# Connectors.net
KiCad netlist of a schematic drawn in Altium Designer
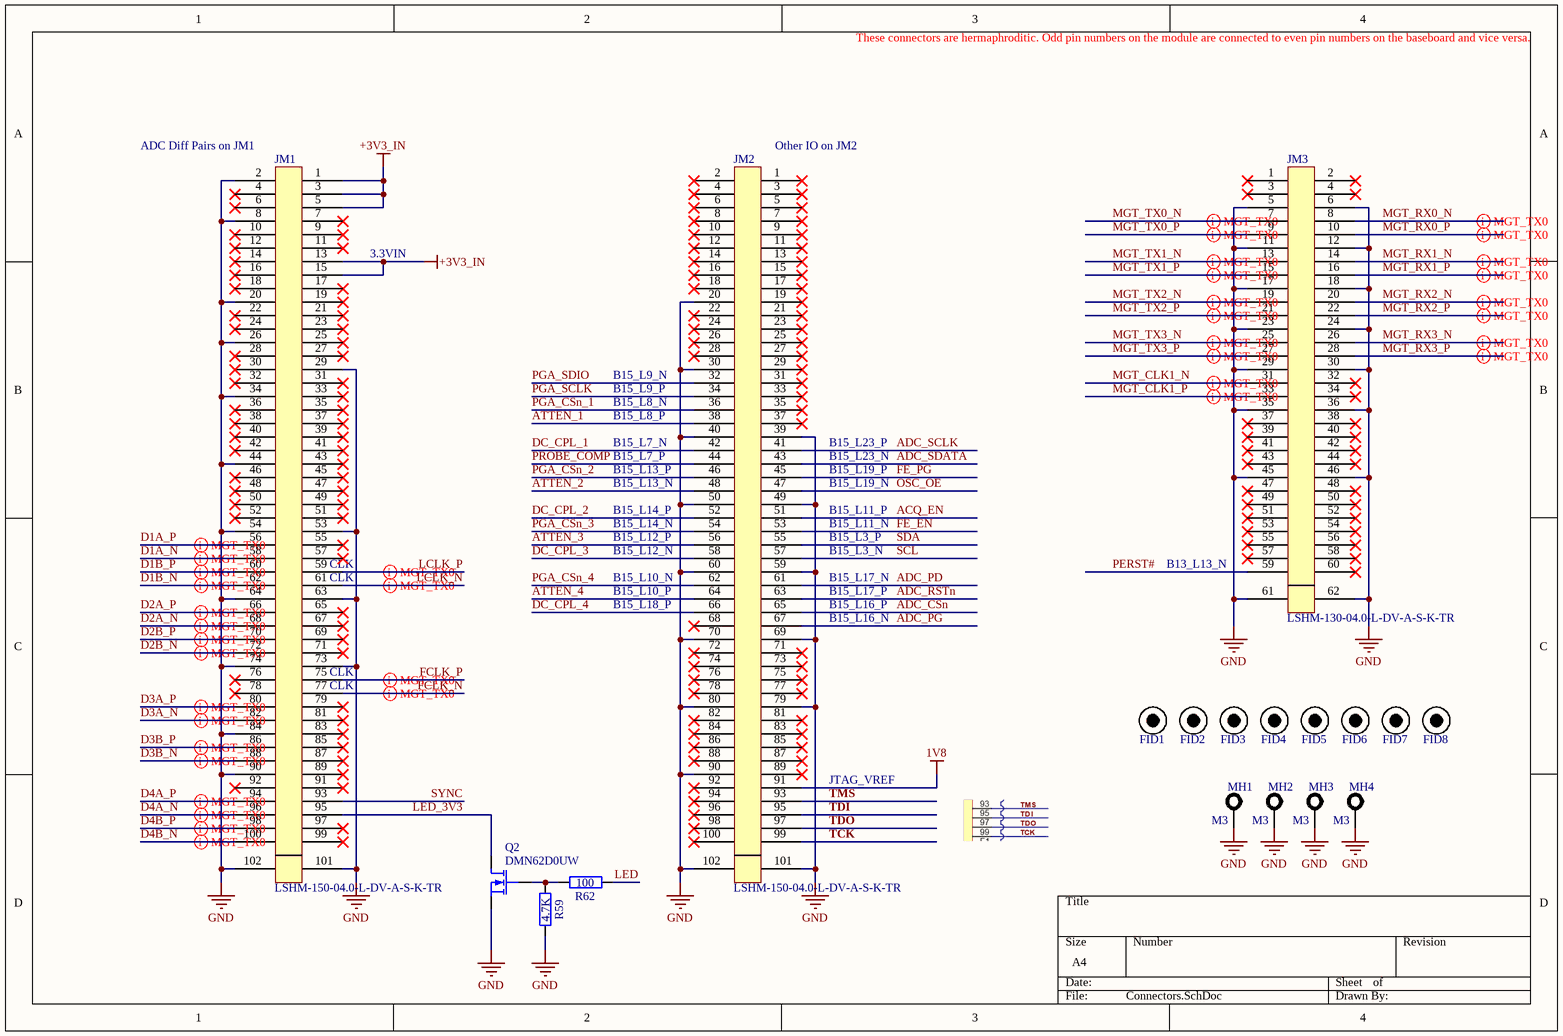
[diagram p0: Connectors.SchDoc]

(export (version "E")
  (design (tool "Eeschema 10.0.6"))
  (components
    (comp (ref "FID1")
      (value "PCB")
      (footprint "GEN_FID")
      (fields (field (name "HOUSE PART NUMBER") "Fiducial-1"))
      (libsource (lib "DSO") (part "FID 1mm"))
    )
    (comp (ref "FID2")
      (value "PCB")
      (footprint "GEN_FID")
      (fields (field (name "HOUSE PART NUMBER") "Fiducial-1"))
      (libsource (lib "DSO") (part "FID 1mm"))
    )
    (comp (ref "FID3")
      (value "PCB")
      (footprint "GEN_FID")
      (fields (field (name "HOUSE PART NUMBER") "Fiducial-1"))
      (libsource (lib "DSO") (part "FID 1mm"))
    )
    (comp (ref "FID4")
      (value "PCB")
      (footprint "GEN_FID")
      (fields (field (name "HOUSE PART NUMBER") "Fiducial-1"))
      (libsource (lib "DSO") (part "FID 1mm"))
    )
    (comp (ref "FID5")
      (value "PCB")
      (footprint "GEN_FID")
      (fields (field (name "HOUSE PART NUMBER") "Fiducial-1"))
      (libsource (lib "DSO") (part "FID 1mm"))
    )
    (comp (ref "FID6")
      (value "PCB")
      (footprint "GEN_FID")
      (fields (field (name "HOUSE PART NUMBER") "Fiducial-1"))
      (libsource (lib "DSO") (part "FID 1mm"))
    )
    (comp (ref "FID7")
      (value "PCB")
      (footprint "GEN_FID")
      (fields (field (name "HOUSE PART NUMBER") "Fiducial-1"))
      (libsource (lib "DSO") (part "FID 1mm"))
    )
    (comp (ref "FID8")
      (value "PCB")
      (footprint "GEN_FID")
      (fields (field (name "HOUSE PART NUMBER") "Fiducial-1"))
      (libsource (lib "DSO") (part "FID 1mm"))
    )
    (comp (ref "JM1")
      (value "LSHM-150-04.0-L-DV-A-S-K-TR")
      (footprint "SAM_LSHM-150-XX.X-XX-DV-A-S")
      (fields (field (name "MANUFACTURER") "Samtec"))
      (libsource (lib "DSO") (part "CONN LSHM-150-04.0-L-DV-A-S-K-TR"))
    )
    (comp (ref "JM2")
      (value "LSHM-150-04.0-L-DV-A-S-K-TR")
      (footprint "SAM_LSHM-150-XX.X-XX-DV-A-S")
      (fields (field (name "MANUFACTURER") "Samtec"))
      (libsource (lib "DSO") (part "CONN LSHM-150-04.0-L-DV-A-S-K-TR"))
    )
    (comp (ref "JM3")
      (value "LSHM-130-04.0-L-DV-A-S-K-TR")
      (footprint "SAM_LSHM-130-XX.X-XX-DV-A-S")
      (fields (field (name "MANUFACTURER") "Samtec"))
      (libsource (lib "DSO") (part "CONN LSHM-130-04.0-L-DV-A-S-K-TR"))
    )
    (comp (ref "MH1") (value "M3") (footprint "MH M3") (libsource (lib "DSO") (part "MH M3")))
    (comp (ref "MH2") (value "M3") (footprint "MH M3") (libsource (lib "DSO") (part "MH M3")))
    (comp (ref "MH3") (value "M3") (footprint "MH M3") (libsource (lib "DSO") (part "MH M3")))
    (comp (ref "MH4") (value "M3") (footprint "MH M3") (libsource (lib "DSO") (part "MH M3")))
    (comp (ref "Q2")
      (value "DMN62D0UW")
      (footprint "GEN_SOT_323")
      (fields (field (name "HOUSE PART NUMBER") "DMN62D0UW-7") (field (name "MANUFACTURER") "Diodes"))
      (libsource (lib "DSO") (part "NMOS DMN62D0UW"))
    )
    (comp (ref "R59")
      (value "4.7K")
      (footprint "GEN_R_0201")
      (fields
        (field (name "TOLERANCE") "1%")
        (field (name "HOUSE PART NUMBER") "R-4.7K-0201-1%-001")
        (field (name "MANUFACTURER") "Yageo")
      )
      (libsource (lib "DSO") (part "RES 4.7K OHM 1% 1/20W 0201"))
    )
    (comp (ref "R62")
      (value "100")
      (footprint "GEN_R_0201")
      (fields
        (field (name "TOLERANCE") "1%")
        (field (name "HOUSE PART NUMBER") "R-100-0201-1%-001")
        (field (name "MANUFACTURER") "Yageo")
      )
      (libsource (lib "DSO") (part "RES 100 OHM 1% 1/20W 0201"))
    )
  )
  (nets
    (net (code "1") (name "+3V3_IN") (class "Default")
      (node (ref "JM1") (pin "1") (pinfunction "1_1") (pintype "passive"))
      (node (ref "JM1") (pin "13") (pinfunction "13_13") (pintype "passive"))
      (node (ref "JM1") (pin "15") (pinfunction "15_15") (pintype "passive"))
      (node (ref "JM1") (pin "3") (pinfunction "3_3") (pintype "passive"))
      (node (ref "JM1") (pin "5") (pinfunction "5_5") (pintype "passive"))
    )
    (net (code "2") (name "/ACQ_EN") (class "Default")
      (node (ref "JM2") (pin "51") (pinfunction "51_51") (pintype "passive"))
    )
    (net (code "3") (name "/ADC_CSn") (class "Default")
      (node (ref "JM2") (pin "65") (pinfunction "65_65") (pintype "passive"))
    )
    (net (code "4") (name "/ADC_PD") (class "Default")
      (node (ref "JM2") (pin "61") (pinfunction "61_61") (pintype "passive"))
    )
    (net (code "5") (name "/ADC_PG") (class "Default")
      (node (ref "JM2") (pin "67") (pinfunction "67_67") (pintype "passive"))
    )
    (net (code "6") (name "/ADC_RSTn") (class "Default")
      (node (ref "JM2") (pin "63") (pinfunction "63_63") (pintype "passive"))
    )
    (net (code "7") (name "/ADC_SCLK") (class "Default")
      (node (ref "JM2") (pin "41") (pinfunction "41_41") (pintype "passive"))
    )
    (net (code "8") (name "/ADC_SDATA") (class "Default")
      (node (ref "JM2") (pin "43") (pinfunction "43_43") (pintype "passive"))
    )
    (net (code "9") (name "/ATTEN_1") (class "Default")
      (node (ref "JM2") (pin "38") (pinfunction "38_38") (pintype "passive"))
    )
    (net (code "10") (name "/ATTEN_2") (class "Default")
      (node (ref "JM2") (pin "48") (pinfunction "48_48") (pintype "passive"))
    )
    (net (code "11") (name "/ATTEN_3") (class "Default")
      (node (ref "JM2") (pin "56") (pinfunction "56_56") (pintype "passive"))
    )
    (net (code "12") (name "/ATTEN_4") (class "Default")
      (node (ref "JM2") (pin "64") (pinfunction "64_64") (pintype "passive"))
    )
    (net (code "13") (name "/D1A_N") (class "Default")
      (node (ref "JM1") (pin "58") (pinfunction "58_58") (pintype "passive"))
    )
    (net (code "14") (name "/D1A_P") (class "Default")
      (node (ref "JM1") (pin "56") (pinfunction "56_56") (pintype "passive"))
    )
    (net (code "15") (name "/D1B_N") (class "Default")
      (node (ref "JM1") (pin "62") (pinfunction "62_62") (pintype "passive"))
    )
    (net (code "16") (name "/D1B_P") (class "Default")
      (node (ref "JM1") (pin "60") (pinfunction "60_60") (pintype "passive"))
    )
    (net (code "17") (name "/D2A_N") (class "Default")
      (node (ref "JM1") (pin "68") (pinfunction "68_68") (pintype "passive"))
    )
    (net (code "18") (name "/D2A_P") (class "Default")
      (node (ref "JM1") (pin "66") (pinfunction "66_66") (pintype "passive"))
    )
    (net (code "19") (name "/D2B_N") (class "Default")
      (node (ref "JM1") (pin "72") (pinfunction "72_72") (pintype "passive"))
    )
    (net (code "20") (name "/D2B_P") (class "Default")
      (node (ref "JM1") (pin "70") (pinfunction "70_70") (pintype "passive"))
    )
    (net (code "21") (name "/D3A_N") (class "Default")
      (node (ref "JM1") (pin "82") (pinfunction "82_82") (pintype "passive"))
    )
    (net (code "22") (name "/D3A_P") (class "Default")
      (node (ref "JM1") (pin "80") (pinfunction "80_80") (pintype "passive"))
    )
    (net (code "23") (name "/D3B_N") (class "Default")
      (node (ref "JM1") (pin "88") (pinfunction "88_88") (pintype "passive"))
    )
    (net (code "24") (name "/D3B_P") (class "Default")
      (node (ref "JM1") (pin "86") (pinfunction "86_86") (pintype "passive"))
    )
    (net (code "25") (name "/D4A_N") (class "Default")
      (node (ref "JM1") (pin "96") (pinfunction "96_96") (pintype "passive"))
    )
    (net (code "26") (name "/D4A_P") (class "Default")
      (node (ref "JM1") (pin "94") (pinfunction "94_94") (pintype "passive"))
    )
    (net (code "27") (name "/D4B_N") (class "Default")
      (node (ref "JM1") (pin "100") (pinfunction "100_100") (pintype "passive"))
    )
    (net (code "28") (name "/D4B_P") (class "Default")
      (node (ref "JM1") (pin "98") (pinfunction "98_98") (pintype "passive"))
    )
    (net (code "29") (name "/DC_CPL_1") (class "Default")
      (node (ref "JM2") (pin "42") (pinfunction "42_42") (pintype "passive"))
    )
    (net (code "30") (name "/DC_CPL_2") (class "Default")
      (node (ref "JM2") (pin "52") (pinfunction "52_52") (pintype "passive"))
    )
    (net (code "31") (name "/DC_CPL_3") (class "Default")
      (node (ref "JM2") (pin "58") (pinfunction "58_58") (pintype "passive"))
    )
    (net (code "32") (name "/DC_CPL_4") (class "Default")
      (node (ref "JM2") (pin "66") (pinfunction "66_66") (pintype "passive"))
    )
    (net (code "33") (name "/FCLK_N") (class "Default")
      (node (ref "JM1") (pin "77") (pinfunction "77_77") (pintype "passive"))
    )
    (net (code "34") (name "/FCLK_P") (class "Default")
      (node (ref "JM1") (pin "75") (pinfunction "75_75") (pintype "passive"))
    )
    (net (code "35") (name "/FE_EN") (class "Default")
      (node (ref "JM2") (pin "53") (pinfunction "53_53") (pintype "passive"))
    )
    (net (code "36") (name "/FE_PG") (class "Default")
      (node (ref "JM2") (pin "45") (pinfunction "45_45") (pintype "passive"))
    )
    (net (code "37") (name "/LCLK_N") (class "Default")
      (node (ref "JM1") (pin "61") (pinfunction "61_61") (pintype "passive"))
    )
    (net (code "38") (name "/LCLK_P") (class "Default")
      (node (ref "JM1") (pin "59") (pinfunction "59_59") (pintype "passive"))
    )
    (net (code "39") (name "/LED") (class "Default")
      (node (ref "R62") (pin "1") (pinfunction "1_1") (pintype "passive"))
    )
    (net (code "40") (name "/LED_3V3") (class "Default")
      (node (ref "JM1") (pin "95") (pinfunction "95_95") (pintype "passive"))
      (node (ref "Q2") (pin "1") (pinfunction "D_1") (pintype "passive"))
    )
    (net (code "41") (name "/MGT_CLK1_N") (class "Default")
      (node (ref "JM3") (pin "31") (pinfunction "31_31") (pintype "passive"))
    )
    (net (code "42") (name "/MGT_CLK1_P") (class "Default")
      (node (ref "JM3") (pin "33") (pinfunction "33_33") (pintype "passive"))
    )
    (net (code "43") (name "/MGT_RX0_N") (class "Default")
      (node (ref "JM3") (pin "8") (pinfunction "8_8") (pintype "passive"))
    )
    (net (code "44") (name "/MGT_RX0_P") (class "Default")
      (node (ref "JM3") (pin "10") (pinfunction "10_10") (pintype "passive"))
    )
    (net (code "45") (name "/MGT_RX1_N") (class "Default")
      (node (ref "JM3") (pin "14") (pinfunction "14_14") (pintype "passive"))
    )
    (net (code "46") (name "/MGT_RX1_P") (class "Default")
      (node (ref "JM3") (pin "16") (pinfunction "16_16") (pintype "passive"))
    )
    (net (code "47") (name "/MGT_RX2_N") (class "Default")
      (node (ref "JM3") (pin "20") (pinfunction "20_20") (pintype "passive"))
    )
    (net (code "48") (name "/MGT_RX2_P") (class "Default")
      (node (ref "JM3") (pin "22") (pinfunction "22_22") (pintype "passive"))
    )
    (net (code "49") (name "/MGT_RX3_N") (class "Default")
      (node (ref "JM3") (pin "26") (pinfunction "26_26") (pintype "passive"))
    )
    (net (code "50") (name "/MGT_RX3_P") (class "Default")
      (node (ref "JM3") (pin "28") (pinfunction "28_28") (pintype "passive"))
    )
    (net (code "51") (name "/MGT_TX0_N") (class "Default")
      (node (ref "JM3") (pin "7") (pinfunction "7_7") (pintype "passive"))
    )
    (net (code "52") (name "/MGT_TX0_P") (class "Default")
      (node (ref "JM3") (pin "9") (pinfunction "9_9") (pintype "passive"))
    )
    (net (code "53") (name "/MGT_TX1_N") (class "Default")
      (node (ref "JM3") (pin "13") (pinfunction "13_13") (pintype "passive"))
    )
    (net (code "54") (name "/MGT_TX1_P") (class "Default")
      (node (ref "JM3") (pin "15") (pinfunction "15_15") (pintype "passive"))
    )
    (net (code "55") (name "/MGT_TX2_N") (class "Default")
      (node (ref "JM3") (pin "19") (pinfunction "19_19") (pintype "passive"))
    )
    (net (code "56") (name "/MGT_TX2_P") (class "Default")
      (node (ref "JM3") (pin "21") (pinfunction "21_21") (pintype "passive"))
    )
    (net (code "57") (name "/MGT_TX3_N") (class "Default")
      (node (ref "JM3") (pin "25") (pinfunction "25_25") (pintype "passive"))
    )
    (net (code "58") (name "/MGT_TX3_P") (class "Default")
      (node (ref "JM3") (pin "27") (pinfunction "27_27") (pintype "passive"))
    )
    (net (code "59") (name "/OSC_OE") (class "Default")
      (node (ref "JM2") (pin "47") (pinfunction "47_47") (pintype "passive"))
    )
    (net (code "60") (name "/PERST#") (class "Default")
      (node (ref "JM3") (pin "59") (pinfunction "59_59") (pintype "passive"))
    )
    (net (code "61") (name "/PGA_CSn_1") (class "Default")
      (node (ref "JM2") (pin "36") (pinfunction "36_36") (pintype "passive"))
    )
    (net (code "62") (name "/PGA_CSn_2") (class "Default")
      (node (ref "JM2") (pin "46") (pinfunction "46_46") (pintype "passive"))
    )
    (net (code "63") (name "/PGA_CSn_3") (class "Default")
      (node (ref "JM2") (pin "54") (pinfunction "54_54") (pintype "passive"))
    )
    (net (code "64") (name "/PGA_CSn_4") (class "Default")
      (node (ref "JM2") (pin "62") (pinfunction "62_62") (pintype "passive"))
    )
    (net (code "65") (name "/PGA_SCLK") (class "Default")
      (node (ref "JM2") (pin "34") (pinfunction "34_34") (pintype "passive"))
    )
    (net (code "66") (name "/PGA_SDIO") (class "Default")
      (node (ref "JM2") (pin "32") (pinfunction "32_32") (pintype "passive"))
    )
    (net (code "67") (name "/PROBE_COMP") (class "Default")
      (node (ref "JM2") (pin "44") (pinfunction "44_44") (pintype "passive"))
    )
    (net (code "68") (name "/SCL") (class "Default")
      (node (ref "JM2") (pin "57") (pinfunction "57_57") (pintype "passive"))
    )
    (net (code "69") (name "/SDA") (class "Default")
      (node (ref "JM2") (pin "55") (pinfunction "55_55") (pintype "passive"))
    )
    (net (code "70") (name "/SYNC") (class "Default")
      (node (ref "JM1") (pin "93") (pinfunction "93_93") (pintype "passive"))
    )
    (net (code "71") (name "/TCK") (class "Default")
      (node (ref "JM2") (pin "99") (pinfunction "99_99") (pintype "passive"))
    )
    (net (code "72") (name "/TDI") (class "Default")
      (node (ref "JM2") (pin "95") (pinfunction "95_95") (pintype "passive"))
    )
    (net (code "73") (name "/TDO") (class "Default")
      (node (ref "JM2") (pin "97") (pinfunction "97_97") (pintype "passive"))
    )
    (net (code "74") (name "/TMS") (class "Default")
      (node (ref "JM2") (pin "93") (pinfunction "93_93") (pintype "passive"))
    )
    (net (code "75") (name "1V8") (class "Default")
      (node (ref "JM2") (pin "91") (pinfunction "91_91") (pintype "passive"))
    )
    (net (code "76") (name "GND") (class "Default")
      (node (ref "JM1") (pin "101") (pinfunction "101_101") (pintype "passive"))
      (node (ref "JM1") (pin "102") (pinfunction "102_102") (pintype "passive"))
      (node (ref "JM1") (pin "2") (pinfunction "2_2") (pintype "passive"))
      (node (ref "JM1") (pin "20") (pinfunction "20_20") (pintype "passive"))
      (node (ref "JM1") (pin "26") (pinfunction "26_26") (pintype "passive"))
      (node (ref "JM1") (pin "29") (pinfunction "29_29") (pintype "passive"))
      (node (ref "JM1") (pin "34") (pinfunction "34_34") (pintype "passive"))
      (node (ref "JM1") (pin "44") (pinfunction "44_44") (pintype "passive"))
      (node (ref "JM1") (pin "53") (pinfunction "53_53") (pintype "passive"))
      (node (ref "JM1") (pin "54") (pinfunction "54_54") (pintype "passive"))
      (node (ref "JM1") (pin "63") (pinfunction "63_63") (pintype "passive"))
      (node (ref "JM1") (pin "64") (pinfunction "64_64") (pintype "passive"))
      (node (ref "JM1") (pin "73") (pinfunction "73_73") (pintype "passive"))
      (node (ref "JM1") (pin "74") (pinfunction "74_74") (pintype "passive"))
      (node (ref "JM1") (pin "8") (pinfunction "8_8") (pintype "passive"))
      (node (ref "JM1") (pin "84") (pinfunction "84_84") (pintype "passive"))
      (node (ref "JM1") (pin "90") (pinfunction "90_90") (pintype "passive"))
      (node (ref "JM2") (pin "101") (pinfunction "101_101") (pintype "passive"))
      (node (ref "JM2") (pin "102") (pinfunction "102_102") (pintype "passive"))
      (node (ref "JM2") (pin "20") (pinfunction "20_20") (pintype "passive"))
      (node (ref "JM2") (pin "30") (pinfunction "30_30") (pintype "passive"))
      (node (ref "JM2") (pin "39") (pinfunction "39_39") (pintype "passive"))
      (node (ref "JM2") (pin "40") (pinfunction "40_40") (pintype "passive"))
      (node (ref "JM2") (pin "49") (pinfunction "49_49") (pintype "passive"))
      (node (ref "JM2") (pin "50") (pinfunction "50_50") (pintype "passive"))
      (node (ref "JM2") (pin "59") (pinfunction "59_59") (pintype "passive"))
      (node (ref "JM2") (pin "60") (pinfunction "60_60") (pintype "passive"))
      (node (ref "JM2") (pin "69") (pinfunction "69_69") (pintype "passive"))
      (node (ref "JM2") (pin "70") (pinfunction "70_70") (pintype "passive"))
      (node (ref "JM2") (pin "79") (pinfunction "79_79") (pintype "passive"))
      (node (ref "JM2") (pin "80") (pinfunction "80_80") (pintype "passive"))
      (node (ref "JM2") (pin "90") (pinfunction "90_90") (pintype "passive"))
      (node (ref "JM3") (pin "11") (pinfunction "11_11") (pintype "passive"))
      (node (ref "JM3") (pin "12") (pinfunction "12_12") (pintype "passive"))
      (node (ref "JM3") (pin "17") (pinfunction "17_17") (pintype "passive"))
      (node (ref "JM3") (pin "18") (pinfunction "18_18") (pintype "passive"))
      (node (ref "JM3") (pin "23") (pinfunction "23_23") (pintype "passive"))
      (node (ref "JM3") (pin "24") (pinfunction "24_24") (pintype "passive"))
      (node (ref "JM3") (pin "29") (pinfunction "29_29") (pintype "passive"))
      (node (ref "JM3") (pin "30") (pinfunction "30_30") (pintype "passive"))
      (node (ref "JM3") (pin "35") (pinfunction "35_35") (pintype "passive"))
      (node (ref "JM3") (pin "36") (pinfunction "36_36") (pintype "passive"))
      (node (ref "JM3") (pin "45") (pinfunction "45_45") (pintype "passive"))
      (node (ref "JM3") (pin "46") (pinfunction "46_46") (pintype "passive"))
      (node (ref "JM3") (pin "5") (pinfunction "5_5") (pintype "passive"))
      (node (ref "JM3") (pin "6") (pinfunction "6_6") (pintype "passive"))
      (node (ref "JM3") (pin "61") (pinfunction "61_61") (pintype "passive"))
      (node (ref "JM3") (pin "62") (pinfunction "62_62") (pintype "passive"))
      (node (ref "MH1") (pin "1") (pinfunction "1_1") (pintype "passive"))
      (node (ref "MH2") (pin "1") (pinfunction "1_1") (pintype "passive"))
      (node (ref "MH3") (pin "1") (pinfunction "1_1") (pintype "passive"))
      (node (ref "MH4") (pin "1") (pinfunction "1_1") (pintype "passive"))
      (node (ref "Q2") (pin "3") (pinfunction "S_3") (pintype "passive"))
      (node (ref "R59") (pin "2") (pinfunction "2_2") (pintype "passive"))
    )
    (net (code "77") (name "Net-(Q2-G)") (class "Default")
      (node (ref "Q2") (pin "2") (pinfunction "G_2") (pintype "passive"))
      (node (ref "R59") (pin "1") (pinfunction "1_1") (pintype "passive"))
      (node (ref "R62") (pin "2") (pinfunction "2_2") (pintype "passive"))
    )
    (net (code "78") (name "unconnected-(JM1-Pad4)") (class "Default")
      (node (ref "JM1") (pin "4") (pinfunction "4_4") (pintype "passive+no_connect"))
    )
    (net (code "79") (name "unconnected-(JM1-Pad6)") (class "Default")
      (node (ref "JM1") (pin "6") (pinfunction "6_6") (pintype "passive+no_connect"))
    )
    (net (code "80") (name "unconnected-(JM1-Pad7)") (class "Default")
      (node (ref "JM1") (pin "7") (pinfunction "7_7") (pintype "passive+no_connect"))
    )
    (net (code "81") (name "unconnected-(JM1-Pad9)") (class "Default")
      (node (ref "JM1") (pin "9") (pinfunction "9_9") (pintype "passive+no_connect"))
    )
    (net (code "82") (name "unconnected-(JM1-Pad10)") (class "Default")
      (node (ref "JM1") (pin "10") (pinfunction "10_10") (pintype "passive+no_connect"))
    )
    (net (code "83") (name "unconnected-(JM1-Pad11)") (class "Default")
      (node (ref "JM1") (pin "11") (pinfunction "11_11") (pintype "passive+no_connect"))
    )
    (net (code "84") (name "unconnected-(JM1-Pad12)") (class "Default")
      (node (ref "JM1") (pin "12") (pinfunction "12_12") (pintype "passive+no_connect"))
    )
    (net (code "85") (name "unconnected-(JM1-Pad14)") (class "Default")
      (node (ref "JM1") (pin "14") (pinfunction "14_14") (pintype "passive+no_connect"))
    )
    (net (code "86") (name "unconnected-(JM1-Pad16)") (class "Default")
      (node (ref "JM1") (pin "16") (pinfunction "16_16") (pintype "passive+no_connect"))
    )
    (net (code "87") (name "unconnected-(JM1-Pad17)") (class "Default")
      (node (ref "JM1") (pin "17") (pinfunction "17_17") (pintype "passive+no_connect"))
    )
    (net (code "88") (name "unconnected-(JM1-Pad18)") (class "Default")
      (node (ref "JM1") (pin "18") (pinfunction "18_18") (pintype "passive+no_connect"))
    )
    (net (code "89") (name "unconnected-(JM1-Pad19)") (class "Default")
      (node (ref "JM1") (pin "19") (pinfunction "19_19") (pintype "passive+no_connect"))
    )
    (net (code "90") (name "unconnected-(JM1-Pad21)") (class "Default")
      (node (ref "JM1") (pin "21") (pinfunction "21_21") (pintype "passive+no_connect"))
    )
    (net (code "91") (name "unconnected-(JM1-Pad22)") (class "Default")
      (node (ref "JM1") (pin "22") (pinfunction "22_22") (pintype "passive+no_connect"))
    )
    (net (code "92") (name "unconnected-(JM1-Pad23)") (class "Default")
      (node (ref "JM1") (pin "23") (pinfunction "23_23") (pintype "passive+no_connect"))
    )
    (net (code "93") (name "unconnected-(JM1-Pad24)") (class "Default")
      (node (ref "JM1") (pin "24") (pinfunction "24_24") (pintype "passive+no_connect"))
    )
    (net (code "94") (name "unconnected-(JM1-Pad25)") (class "Default")
      (node (ref "JM1") (pin "25") (pinfunction "25_25") (pintype "passive+no_connect"))
    )
    (net (code "95") (name "unconnected-(JM1-Pad27)") (class "Default")
      (node (ref "JM1") (pin "27") (pinfunction "27_27") (pintype "passive+no_connect"))
    )
    (net (code "96") (name "unconnected-(JM1-Pad28)") (class "Default")
      (node (ref "JM1") (pin "28") (pinfunction "28_28") (pintype "passive+no_connect"))
    )
    (net (code "97") (name "unconnected-(JM1-Pad30)") (class "Default")
      (node (ref "JM1") (pin "30") (pinfunction "30_30") (pintype "passive+no_connect"))
    )
    (net (code "98") (name "unconnected-(JM1-Pad31)") (class "Default")
      (node (ref "JM1") (pin "31") (pinfunction "31_31") (pintype "passive+no_connect"))
    )
    (net (code "99") (name "unconnected-(JM1-Pad32)") (class "Default")
      (node (ref "JM1") (pin "32") (pinfunction "32_32") (pintype "passive+no_connect"))
    )
    (net (code "100") (name "unconnected-(JM1-Pad33)") (class "Default")
      (node (ref "JM1") (pin "33") (pinfunction "33_33") (pintype "passive+no_connect"))
    )
    (net (code "101") (name "unconnected-(JM1-Pad35)") (class "Default")
      (node (ref "JM1") (pin "35") (pinfunction "35_35") (pintype "passive+no_connect"))
    )
    (net (code "102") (name "unconnected-(JM1-Pad36)") (class "Default")
      (node (ref "JM1") (pin "36") (pinfunction "36_36") (pintype "passive+no_connect"))
    )
    (net (code "103") (name "unconnected-(JM1-Pad37)") (class "Default")
      (node (ref "JM1") (pin "37") (pinfunction "37_37") (pintype "passive+no_connect"))
    )
    (net (code "104") (name "unconnected-(JM1-Pad38)") (class "Default")
      (node (ref "JM1") (pin "38") (pinfunction "38_38") (pintype "passive+no_connect"))
    )
    (net (code "105") (name "unconnected-(JM1-Pad39)") (class "Default")
      (node (ref "JM1") (pin "39") (pinfunction "39_39") (pintype "passive+no_connect"))
    )
    (net (code "106") (name "unconnected-(JM1-Pad40)") (class "Default")
      (node (ref "JM1") (pin "40") (pinfunction "40_40") (pintype "passive+no_connect"))
    )
    (net (code "107") (name "unconnected-(JM1-Pad41)") (class "Default")
      (node (ref "JM1") (pin "41") (pinfunction "41_41") (pintype "passive+no_connect"))
    )
    (net (code "108") (name "unconnected-(JM1-Pad42)") (class "Default")
      (node (ref "JM1") (pin "42") (pinfunction "42_42") (pintype "passive+no_connect"))
    )
    (net (code "109") (name "unconnected-(JM1-Pad43)") (class "Default")
      (node (ref "JM1") (pin "43") (pinfunction "43_43") (pintype "passive+no_connect"))
    )
    (net (code "110") (name "unconnected-(JM1-Pad45)") (class "Default")
      (node (ref "JM1") (pin "45") (pinfunction "45_45") (pintype "passive+no_connect"))
    )
    (net (code "111") (name "unconnected-(JM1-Pad46)") (class "Default")
      (node (ref "JM1") (pin "46") (pinfunction "46_46") (pintype "passive+no_connect"))
    )
    (net (code "112") (name "unconnected-(JM1-Pad47)") (class "Default")
      (node (ref "JM1") (pin "47") (pinfunction "47_47") (pintype "passive+no_connect"))
    )
    (net (code "113") (name "unconnected-(JM1-Pad48)") (class "Default")
      (node (ref "JM1") (pin "48") (pinfunction "48_48") (pintype "passive+no_connect"))
    )
    (net (code "114") (name "unconnected-(JM1-Pad49)") (class "Default")
      (node (ref "JM1") (pin "49") (pinfunction "49_49") (pintype "passive+no_connect"))
    )
    (net (code "115") (name "unconnected-(JM1-Pad50)") (class "Default")
      (node (ref "JM1") (pin "50") (pinfunction "50_50") (pintype "passive+no_connect"))
    )
    (net (code "116") (name "unconnected-(JM1-Pad51)") (class "Default")
      (node (ref "JM1") (pin "51") (pinfunction "51_51") (pintype "passive+no_connect"))
    )
    (net (code "117") (name "unconnected-(JM1-Pad52)") (class "Default")
      (node (ref "JM1") (pin "52") (pinfunction "52_52") (pintype "passive+no_connect"))
    )
    (net (code "118") (name "unconnected-(JM1-Pad55)") (class "Default")
      (node (ref "JM1") (pin "55") (pinfunction "55_55") (pintype "passive+no_connect"))
    )
    (net (code "119") (name "unconnected-(JM1-Pad57)") (class "Default")
      (node (ref "JM1") (pin "57") (pinfunction "57_57") (pintype "passive+no_connect"))
    )
    (net (code "120") (name "unconnected-(JM1-Pad65)") (class "Default")
      (node (ref "JM1") (pin "65") (pinfunction "65_65") (pintype "passive+no_connect"))
    )
    (net (code "121") (name "unconnected-(JM1-Pad67)") (class "Default")
      (node (ref "JM1") (pin "67") (pinfunction "67_67") (pintype "passive+no_connect"))
    )
    (net (code "122") (name "unconnected-(JM1-Pad69)") (class "Default")
      (node (ref "JM1") (pin "69") (pinfunction "69_69") (pintype "passive+no_connect"))
    )
    (net (code "123") (name "unconnected-(JM1-Pad71)") (class "Default")
      (node (ref "JM1") (pin "71") (pinfunction "71_71") (pintype "passive+no_connect"))
    )
    (net (code "124") (name "unconnected-(JM1-Pad76)") (class "Default")
      (node (ref "JM1") (pin "76") (pinfunction "76_76") (pintype "passive+no_connect"))
    )
    (net (code "125") (name "unconnected-(JM1-Pad78)") (class "Default")
      (node (ref "JM1") (pin "78") (pinfunction "78_78") (pintype "passive+no_connect"))
    )
    (net (code "126") (name "unconnected-(JM1-Pad79)") (class "Default")
      (node (ref "JM1") (pin "79") (pinfunction "79_79") (pintype "passive+no_connect"))
    )
    (net (code "127") (name "unconnected-(JM1-Pad81)") (class "Default")
      (node (ref "JM1") (pin "81") (pinfunction "81_81") (pintype "passive+no_connect"))
    )
    (net (code "128") (name "unconnected-(JM1-Pad83)") (class "Default")
      (node (ref "JM1") (pin "83") (pinfunction "83_83") (pintype "passive+no_connect"))
    )
    (net (code "129") (name "unconnected-(JM1-Pad85)") (class "Default")
      (node (ref "JM1") (pin "85") (pinfunction "85_85") (pintype "passive+no_connect"))
    )
    (net (code "130") (name "unconnected-(JM1-Pad87)") (class "Default")
      (node (ref "JM1") (pin "87") (pinfunction "87_87") (pintype "passive+no_connect"))
    )
    (net (code "131") (name "unconnected-(JM1-Pad89)") (class "Default")
      (node (ref "JM1") (pin "89") (pinfunction "89_89") (pintype "passive+no_connect"))
    )
    (net (code "132") (name "unconnected-(JM1-Pad91)") (class "Default")
      (node (ref "JM1") (pin "91") (pinfunction "91_91") (pintype "passive+no_connect"))
    )
    (net (code "133") (name "unconnected-(JM1-Pad92)") (class "Default")
      (node (ref "JM1") (pin "92") (pinfunction "92_92") (pintype "passive+no_connect"))
    )
    (net (code "134") (name "unconnected-(JM1-Pad97)") (class "Default")
      (node (ref "JM1") (pin "97") (pinfunction "97_97") (pintype "passive+no_connect"))
    )
    (net (code "135") (name "unconnected-(JM1-Pad99)") (class "Default")
      (node (ref "JM1") (pin "99") (pinfunction "99_99") (pintype "passive+no_connect"))
    )
    (net (code "136") (name "unconnected-(JM2-Pad1)") (class "Default")
      (node (ref "JM2") (pin "1") (pinfunction "1_1") (pintype "passive+no_connect"))
    )
    (net (code "137") (name "unconnected-(JM2-Pad2)") (class "Default")
      (node (ref "JM2") (pin "2") (pinfunction "2_2") (pintype "passive+no_connect"))
    )
    (net (code "138") (name "unconnected-(JM2-Pad3)") (class "Default")
      (node (ref "JM2") (pin "3") (pinfunction "3_3") (pintype "passive+no_connect"))
    )
    (net (code "139") (name "unconnected-(JM2-Pad4)") (class "Default")
      (node (ref "JM2") (pin "4") (pinfunction "4_4") (pintype "passive+no_connect"))
    )
    (net (code "140") (name "unconnected-(JM2-Pad5)") (class "Default")
      (node (ref "JM2") (pin "5") (pinfunction "5_5") (pintype "passive+no_connect"))
    )
    (net (code "141") (name "unconnected-(JM2-Pad6)") (class "Default")
      (node (ref "JM2") (pin "6") (pinfunction "6_6") (pintype "passive+no_connect"))
    )
    (net (code "142") (name "unconnected-(JM2-Pad7)") (class "Default")
      (node (ref "JM2") (pin "7") (pinfunction "7_7") (pintype "passive+no_connect"))
    )
    (net (code "143") (name "unconnected-(JM2-Pad8)") (class "Default")
      (node (ref "JM2") (pin "8") (pinfunction "8_8") (pintype "passive+no_connect"))
    )
    (net (code "144") (name "unconnected-(JM2-Pad9)") (class "Default")
      (node (ref "JM2") (pin "9") (pinfunction "9_9") (pintype "passive+no_connect"))
    )
    (net (code "145") (name "unconnected-(JM2-Pad10)") (class "Default")
      (node (ref "JM2") (pin "10") (pinfunction "10_10") (pintype "passive+no_connect"))
    )
    (net (code "146") (name "unconnected-(JM2-Pad11)") (class "Default")
      (node (ref "JM2") (pin "11") (pinfunction "11_11") (pintype "passive+no_connect"))
    )
    (net (code "147") (name "unconnected-(JM2-Pad12)") (class "Default")
      (node (ref "JM2") (pin "12") (pinfunction "12_12") (pintype "passive+no_connect"))
    )
    (net (code "148") (name "unconnected-(JM2-Pad13)") (class "Default")
      (node (ref "JM2") (pin "13") (pinfunction "13_13") (pintype "passive+no_connect"))
    )
    (net (code "149") (name "unconnected-(JM2-Pad14)") (class "Default")
      (node (ref "JM2") (pin "14") (pinfunction "14_14") (pintype "passive+no_connect"))
    )
    (net (code "150") (name "unconnected-(JM2-Pad15)") (class "Default")
      (node (ref "JM2") (pin "15") (pinfunction "15_15") (pintype "passive+no_connect"))
    )
    (net (code "151") (name "unconnected-(JM2-Pad16)") (class "Default")
      (node (ref "JM2") (pin "16") (pinfunction "16_16") (pintype "passive+no_connect"))
    )
    (net (code "152") (name "unconnected-(JM2-Pad17)") (class "Default")
      (node (ref "JM2") (pin "17") (pinfunction "17_17") (pintype "passive+no_connect"))
    )
    (net (code "153") (name "unconnected-(JM2-Pad18)") (class "Default")
      (node (ref "JM2") (pin "18") (pinfunction "18_18") (pintype "passive+no_connect"))
    )
    (net (code "154") (name "unconnected-(JM2-Pad19)") (class "Default")
      (node (ref "JM2") (pin "19") (pinfunction "19_19") (pintype "passive+no_connect"))
    )
    (net (code "155") (name "unconnected-(JM2-Pad21)") (class "Default")
      (node (ref "JM2") (pin "21") (pinfunction "21_21") (pintype "passive+no_connect"))
    )
    (net (code "156") (name "unconnected-(JM2-Pad22)") (class "Default")
      (node (ref "JM2") (pin "22") (pinfunction "22_22") (pintype "passive+no_connect"))
    )
    (net (code "157") (name "unconnected-(JM2-Pad23)") (class "Default")
      (node (ref "JM2") (pin "23") (pinfunction "23_23") (pintype "passive+no_connect"))
    )
    (net (code "158") (name "unconnected-(JM2-Pad24)") (class "Default")
      (node (ref "JM2") (pin "24") (pinfunction "24_24") (pintype "passive+no_connect"))
    )
    (net (code "159") (name "unconnected-(JM2-Pad25)") (class "Default")
      (node (ref "JM2") (pin "25") (pinfunction "25_25") (pintype "passive+no_connect"))
    )
    (net (code "160") (name "unconnected-(JM2-Pad26)") (class "Default")
      (node (ref "JM2") (pin "26") (pinfunction "26_26") (pintype "passive+no_connect"))
    )
    (net (code "161") (name "unconnected-(JM2-Pad27)") (class "Default")
      (node (ref "JM2") (pin "27") (pinfunction "27_27") (pintype "passive+no_connect"))
    )
    (net (code "162") (name "unconnected-(JM2-Pad28)") (class "Default")
      (node (ref "JM2") (pin "28") (pinfunction "28_28") (pintype "passive+no_connect"))
    )
    (net (code "163") (name "unconnected-(JM2-Pad29)") (class "Default")
      (node (ref "JM2") (pin "29") (pinfunction "29_29") (pintype "passive+no_connect"))
    )
    (net (code "164") (name "unconnected-(JM2-Pad31)") (class "Default")
      (node (ref "JM2") (pin "31") (pinfunction "31_31") (pintype "passive+no_connect"))
    )
    (net (code "165") (name "unconnected-(JM2-Pad33)") (class "Default")
      (node (ref "JM2") (pin "33") (pinfunction "33_33") (pintype "passive+no_connect"))
    )
    (net (code "166") (name "unconnected-(JM2-Pad35)") (class "Default")
      (node (ref "JM2") (pin "35") (pinfunction "35_35") (pintype "passive+no_connect"))
    )
    (net (code "167") (name "unconnected-(JM2-Pad37)") (class "Default")
      (node (ref "JM2") (pin "37") (pinfunction "37_37") (pintype "passive+no_connect"))
    )
    (net (code "168") (name "unconnected-(JM2-Pad68)") (class "Default")
      (node (ref "JM2") (pin "68") (pinfunction "68_68") (pintype "passive+no_connect"))
    )
    (net (code "169") (name "unconnected-(JM2-Pad71)") (class "Default")
      (node (ref "JM2") (pin "71") (pinfunction "71_71") (pintype "passive+no_connect"))
    )
    (net (code "170") (name "unconnected-(JM2-Pad72)") (class "Default")
      (node (ref "JM2") (pin "72") (pinfunction "72_72") (pintype "passive+no_connect"))
    )
    (net (code "171") (name "unconnected-(JM2-Pad73)") (class "Default")
      (node (ref "JM2") (pin "73") (pinfunction "73_73") (pintype "passive+no_connect"))
    )
    (net (code "172") (name "unconnected-(JM2-Pad74)") (class "Default")
      (node (ref "JM2") (pin "74") (pinfunction "74_74") (pintype "passive+no_connect"))
    )
    (net (code "173") (name "unconnected-(JM2-Pad75)") (class "Default")
      (node (ref "JM2") (pin "75") (pinfunction "75_75") (pintype "passive+no_connect"))
    )
    (net (code "174") (name "unconnected-(JM2-Pad76)") (class "Default")
      (node (ref "JM2") (pin "76") (pinfunction "76_76") (pintype "passive+no_connect"))
    )
    (net (code "175") (name "unconnected-(JM2-Pad77)") (class "Default")
      (node (ref "JM2") (pin "77") (pinfunction "77_77") (pintype "passive+no_connect"))
    )
    (net (code "176") (name "unconnected-(JM2-Pad78)") (class "Default")
      (node (ref "JM2") (pin "78") (pinfunction "78_78") (pintype "passive+no_connect"))
    )
    (net (code "177") (name "unconnected-(JM2-Pad81)") (class "Default")
      (node (ref "JM2") (pin "81") (pinfunction "81_81") (pintype "passive+no_connect"))
    )
    (net (code "178") (name "unconnected-(JM2-Pad82)") (class "Default")
      (node (ref "JM2") (pin "82") (pinfunction "82_82") (pintype "passive+no_connect"))
    )
    (net (code "179") (name "unconnected-(JM2-Pad83)") (class "Default")
      (node (ref "JM2") (pin "83") (pinfunction "83_83") (pintype "passive+no_connect"))
    )
    (net (code "180") (name "unconnected-(JM2-Pad84)") (class "Default")
      (node (ref "JM2") (pin "84") (pinfunction "84_84") (pintype "passive+no_connect"))
    )
    (net (code "181") (name "unconnected-(JM2-Pad85)") (class "Default")
      (node (ref "JM2") (pin "85") (pinfunction "85_85") (pintype "passive+no_connect"))
    )
    (net (code "182") (name "unconnected-(JM2-Pad86)") (class "Default")
      (node (ref "JM2") (pin "86") (pinfunction "86_86") (pintype "passive+no_connect"))
    )
    (net (code "183") (name "unconnected-(JM2-Pad87)") (class "Default")
      (node (ref "JM2") (pin "87") (pinfunction "87_87") (pintype "passive+no_connect"))
    )
    (net (code "184") (name "unconnected-(JM2-Pad88)") (class "Default")
      (node (ref "JM2") (pin "88") (pinfunction "88_88") (pintype "passive+no_connect"))
    )
    (net (code "185") (name "unconnected-(JM2-Pad89)") (class "Default")
      (node (ref "JM2") (pin "89") (pinfunction "89_89") (pintype "passive+no_connect"))
    )
    (net (code "186") (name "unconnected-(JM2-Pad92)") (class "Default")
      (node (ref "JM2") (pin "92") (pinfunction "92_92") (pintype "passive+no_connect"))
    )
    (net (code "187") (name "unconnected-(JM2-Pad94)") (class "Default")
      (node (ref "JM2") (pin "94") (pinfunction "94_94") (pintype "passive+no_connect"))
    )
    (net (code "188") (name "unconnected-(JM2-Pad96)") (class "Default")
      (node (ref "JM2") (pin "96") (pinfunction "96_96") (pintype "passive+no_connect"))
    )
    (net (code "189") (name "unconnected-(JM2-Pad98)") (class "Default")
      (node (ref "JM2") (pin "98") (pinfunction "98_98") (pintype "passive+no_connect"))
    )
    (net (code "190") (name "unconnected-(JM2-Pad100)") (class "Default")
      (node (ref "JM2") (pin "100") (pinfunction "100_100") (pintype "passive+no_connect"))
    )
    (net (code "191") (name "unconnected-(JM3-Pad1)") (class "Default")
      (node (ref "JM3") (pin "1") (pinfunction "1_1") (pintype "passive+no_connect"))
    )
    (net (code "192") (name "unconnected-(JM3-Pad2)") (class "Default")
      (node (ref "JM3") (pin "2") (pinfunction "2_2") (pintype "passive+no_connect"))
    )
    (net (code "193") (name "unconnected-(JM3-Pad3)") (class "Default")
      (node (ref "JM3") (pin "3") (pinfunction "3_3") (pintype "passive+no_connect"))
    )
    (net (code "194") (name "unconnected-(JM3-Pad4)") (class "Default")
      (node (ref "JM3") (pin "4") (pinfunction "4_4") (pintype "passive+no_connect"))
    )
    (net (code "195") (name "unconnected-(JM3-Pad32)") (class "Default")
      (node (ref "JM3") (pin "32") (pinfunction "32_32") (pintype "passive+no_connect"))
    )
    (net (code "196") (name "unconnected-(JM3-Pad34)") (class "Default")
      (node (ref "JM3") (pin "34") (pinfunction "34_34") (pintype "passive+no_connect"))
    )
    (net (code "197") (name "unconnected-(JM3-Pad37)") (class "Default")
      (node (ref "JM3") (pin "37") (pinfunction "37_37") (pintype "passive+no_connect"))
    )
    (net (code "198") (name "unconnected-(JM3-Pad38)") (class "Default")
      (node (ref "JM3") (pin "38") (pinfunction "38_38") (pintype "passive+no_connect"))
    )
    (net (code "199") (name "unconnected-(JM3-Pad39)") (class "Default")
      (node (ref "JM3") (pin "39") (pinfunction "39_39") (pintype "passive+no_connect"))
    )
    (net (code "200") (name "unconnected-(JM3-Pad40)") (class "Default")
      (node (ref "JM3") (pin "40") (pinfunction "40_40") (pintype "passive+no_connect"))
    )
    (net (code "201") (name "unconnected-(JM3-Pad41)") (class "Default")
      (node (ref "JM3") (pin "41") (pinfunction "41_41") (pintype "passive+no_connect"))
    )
    (net (code "202") (name "unconnected-(JM3-Pad42)") (class "Default")
      (node (ref "JM3") (pin "42") (pinfunction "42_42") (pintype "passive+no_connect"))
    )
    (net (code "203") (name "unconnected-(JM3-Pad43)") (class "Default")
      (node (ref "JM3") (pin "43") (pinfunction "43_43") (pintype "passive+no_connect"))
    )
    (net (code "204") (name "unconnected-(JM3-Pad44)") (class "Default")
      (node (ref "JM3") (pin "44") (pinfunction "44_44") (pintype "passive+no_connect"))
    )
    (net (code "205") (name "unconnected-(JM3-Pad47)") (class "Default")
      (node (ref "JM3") (pin "47") (pinfunction "47_47") (pintype "passive+no_connect"))
    )
    (net (code "206") (name "unconnected-(JM3-Pad48)") (class "Default")
      (node (ref "JM3") (pin "48") (pinfunction "48_48") (pintype "passive+no_connect"))
    )
    (net (code "207") (name "unconnected-(JM3-Pad49)") (class "Default")
      (node (ref "JM3") (pin "49") (pinfunction "49_49") (pintype "passive+no_connect"))
    )
    (net (code "208") (name "unconnected-(JM3-Pad50)") (class "Default")
      (node (ref "JM3") (pin "50") (pinfunction "50_50") (pintype "passive+no_connect"))
    )
    (net (code "209") (name "unconnected-(JM3-Pad51)") (class "Default")
      (node (ref "JM3") (pin "51") (pinfunction "51_51") (pintype "passive+no_connect"))
    )
    (net (code "210") (name "unconnected-(JM3-Pad52)") (class "Default")
      (node (ref "JM3") (pin "52") (pinfunction "52_52") (pintype "passive+no_connect"))
    )
    (net (code "211") (name "unconnected-(JM3-Pad53)") (class "Default")
      (node (ref "JM3") (pin "53") (pinfunction "53_53") (pintype "passive+no_connect"))
    )
    (net (code "212") (name "unconnected-(JM3-Pad54)") (class "Default")
      (node (ref "JM3") (pin "54") (pinfunction "54_54") (pintype "passive+no_connect"))
    )
    (net (code "213") (name "unconnected-(JM3-Pad55)") (class "Default")
      (node (ref "JM3") (pin "55") (pinfunction "55_55") (pintype "passive+no_connect"))
    )
    (net (code "214") (name "unconnected-(JM3-Pad56)") (class "Default")
      (node (ref "JM3") (pin "56") (pinfunction "56_56") (pintype "passive+no_connect"))
    )
    (net (code "215") (name "unconnected-(JM3-Pad57)") (class "Default")
      (node (ref "JM3") (pin "57") (pinfunction "57_57") (pintype "passive+no_connect"))
    )
    (net (code "216") (name "unconnected-(JM3-Pad58)") (class "Default")
      (node (ref "JM3") (pin "58") (pinfunction "58_58") (pintype "passive+no_connect"))
    )
    (net (code "217") (name "unconnected-(JM3-Pad60)") (class "Default")
      (node (ref "JM3") (pin "60") (pinfunction "60_60") (pintype "passive+no_connect"))
    )
  )
)
